# Low_Voltage_Solar_Controller_V1_1.net
KiCad netlist of a schematic drawn in EAGLE
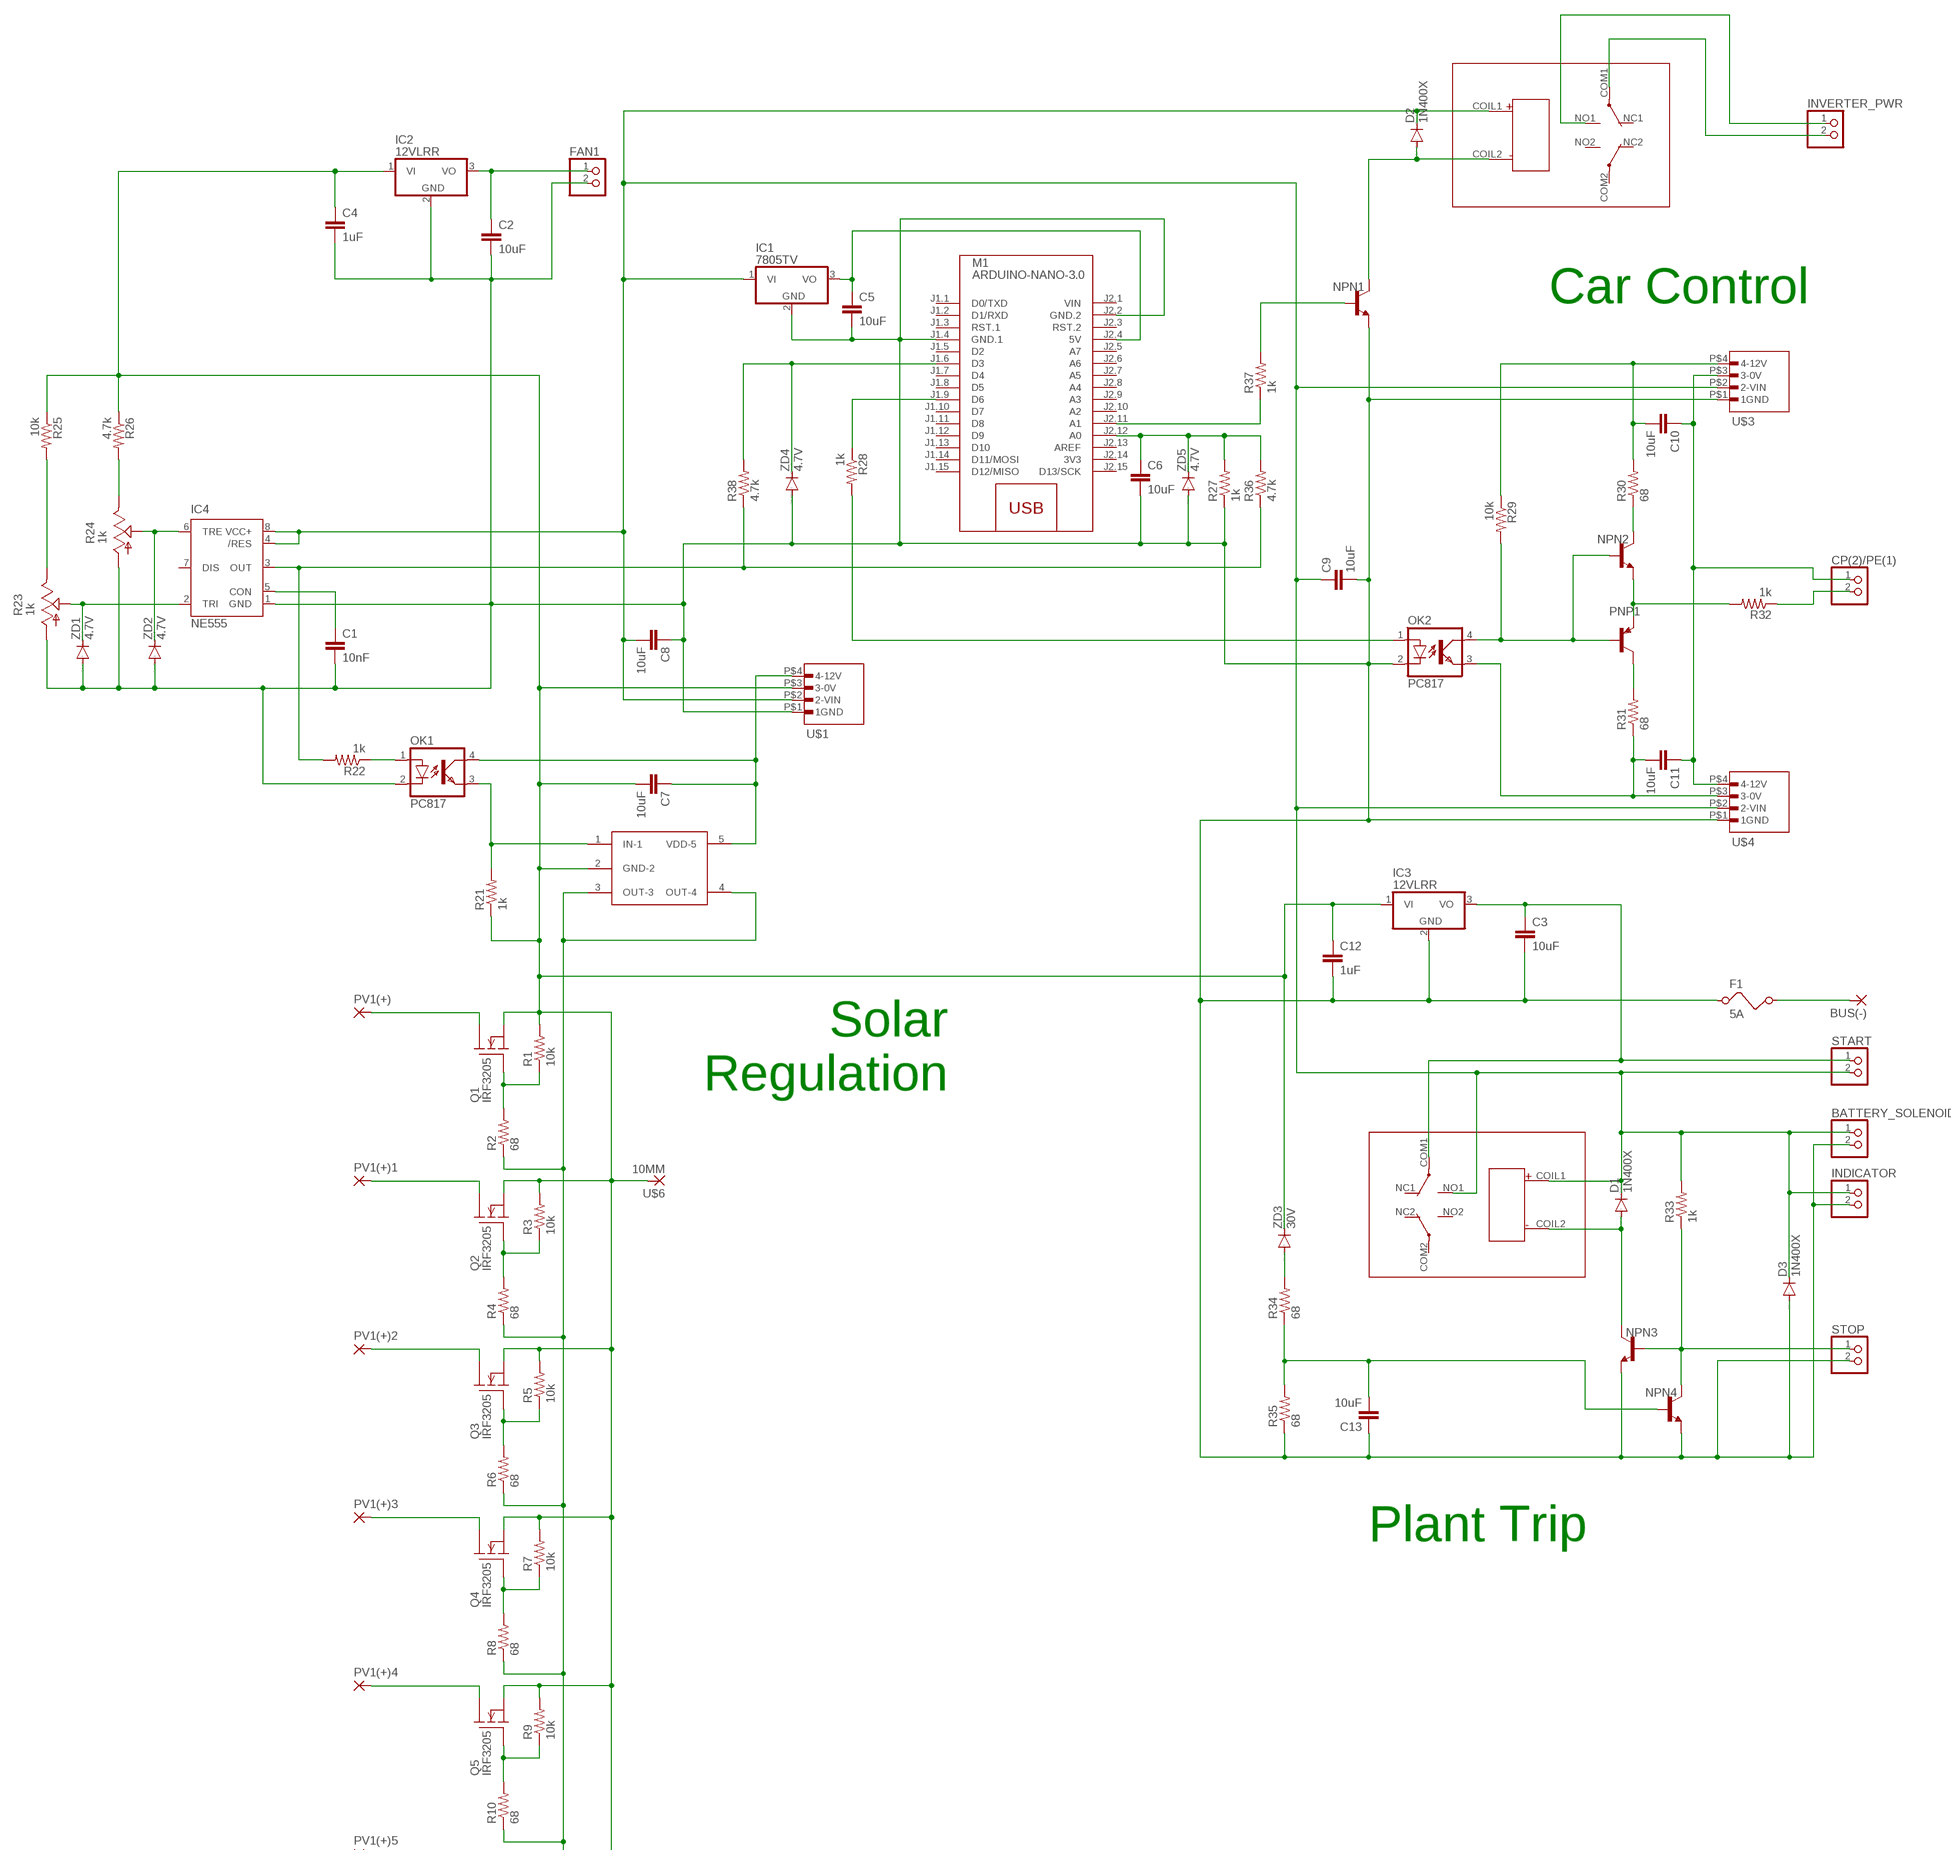
[diagram p0: schematic, sheet 1, part 1 of 2]
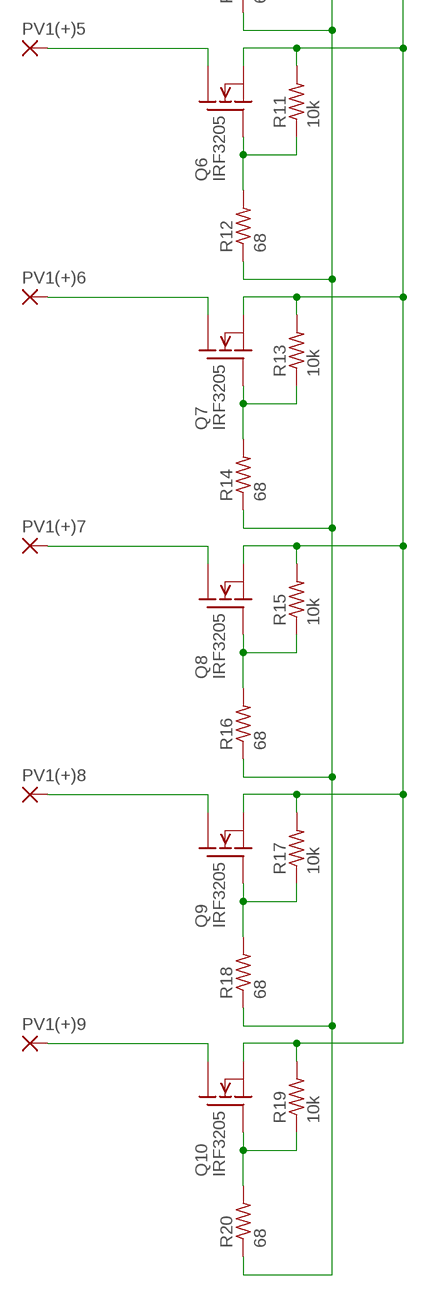
[diagram p1: schematic, sheet 1, part 2 of 2]

(export (version "E")
  (design (tool "Eeschema 10.0.6"))
  (components
    (comp (ref "BATTERY_SOLENOID")
      (value "PINHD-1X2")
      (footprint "eagle-import:1X02")
      (libsource (lib "eagle-import") (part "PINHD-1X2"))
    )
    (comp (ref "BUS(-)")
      (value "5MM_PAD")
      (footprint "eagle-import:5MM")
      (libsource (lib "eagle-import") (part "5MM_PAD"))
    )
    (comp (ref "C1")
      (value "10nF")
      (footprint "eagle-import:C0603")
      (libsource (lib "eagle-import") (part "C-EUC0603"))
    )
    (comp (ref "C2")
      (value "10uF")
      (footprint "eagle-import:C0805")
      (libsource (lib "eagle-import") (part "C-EUC0805"))
    )
    (comp (ref "C3")
      (value "10uF")
      (footprint "eagle-import:C0805")
      (libsource (lib "eagle-import") (part "C-EUC0805"))
    )
    (comp (ref "C4")
      (value "1uF")
      (footprint "eagle-import:C0805")
      (libsource (lib "eagle-import") (part "C-EUC0805"))
    )
    (comp (ref "C5")
      (value "10uF")
      (footprint "eagle-import:C0805")
      (libsource (lib "eagle-import") (part "C-EUC0805"))
    )
    (comp (ref "C6")
      (value "10uF")
      (footprint "eagle-import:C0805")
      (libsource (lib "eagle-import") (part "C-EUC0805"))
    )
    (comp (ref "C7")
      (value "10uF")
      (footprint "eagle-import:C0805")
      (libsource (lib "eagle-import") (part "C-EUC0805"))
    )
    (comp (ref "C8")
      (value "10uF")
      (footprint "eagle-import:C0805")
      (libsource (lib "eagle-import") (part "C-EUC0805"))
    )
    (comp (ref "C9")
      (value "10uF")
      (footprint "eagle-import:C0805")
      (libsource (lib "eagle-import") (part "C-EUC0805"))
    )
    (comp (ref "C10")
      (value "10uF")
      (footprint "eagle-import:C0805")
      (libsource (lib "eagle-import") (part "C-EUC0805"))
    )
    (comp (ref "C11")
      (value "10uF")
      (footprint "eagle-import:C0805")
      (libsource (lib "eagle-import") (part "C-EUC0805"))
    )
    (comp (ref "C12")
      (value "1uF")
      (footprint "eagle-import:C0805")
      (libsource (lib "eagle-import") (part "C-EUC0805"))
    )
    (comp (ref "C13")
      (value "10uF")
      (footprint "eagle-import:C0805")
      (libsource (lib "eagle-import") (part "C-EUC0805"))
    )
    (comp (ref "CP(2)/PE(1)")
      (value "PINHD-1X2")
      (footprint "eagle-import:1X02")
      (libsource (lib "eagle-import") (part "PINHD-1X2"))
    )
    (comp (ref "D1")
      (value "1N400X")
      (footprint "eagle-import:DO41-10")
      (libsource (lib "eagle-import") (part "1N4004"))
    )
    (comp (ref "D2")
      (value "1N400X")
      (footprint "eagle-import:DO41-10")
      (libsource (lib "eagle-import") (part "1N4004"))
    )
    (comp (ref "D3")
      (value "1N400X")
      (footprint "eagle-import:DO41-10")
      (libsource (lib "eagle-import") (part "1N4004"))
    )
    (comp (ref "F1")
      (value "5A")
      (footprint "eagle-import:FUSE_HOLDER")
      (libsource (lib "eagle-import") (part "FUSE_HOLDER"))
    )
    (comp (ref "FAN1")
      (value "PINHD-1X2")
      (footprint "eagle-import:1X02")
      (libsource (lib "eagle-import") (part "PINHD-1X2"))
    )
    (comp (ref "IC1")
      (value "7805TV")
      (footprint "eagle-import:TO220V")
      (libsource (lib "eagle-import") (part "78TV05"))
    )
    (comp (ref "IC2")
      (value "12VLRR")
      (footprint "eagle-import:TO220V")
      (libsource (lib "eagle-import") (part "78TV05"))
    )
    (comp (ref "IC3")
      (value "12VLRR")
      (footprint "eagle-import:TO220V")
      (libsource (lib "eagle-import") (part "78TV05"))
    )
    (comp (ref "IC4")
      (value "NE555")
      (footprint "eagle-import:DIL-08")
      (fields (field (name "MF") "Arrow Electronics") (field (name "MPN") "NE555N"))
      (libsource (lib "eagle-import") (part "NE555"))
    )
    (comp (ref "INDICATOR")
      (value "PINHD-1X2")
      (footprint "eagle-import:1X02")
      (libsource (lib "eagle-import") (part "PINHD-1X2"))
    )
    (comp (ref "INVERTER_PWR")
      (value "PINHD-1X2")
      (footprint "eagle-import:1X02")
      (libsource (lib "eagle-import") (part "PINHD-1X2"))
    )
    (comp (ref "M1")
      (value "ARDUINO-NANO-3.0")
      (footprint "eagle-import:ARDUINO-NANO-3.0")
      (libsource (lib "eagle-import") (part "ARDUINO-NANO-3.0"))
    )
    (comp (ref "NPN1")
      (value "-NPN-TO92-EBC")
      (footprint "eagle-import:TO92-EBC")
      (libsource (lib "eagle-import") (part "-NPN-TO92-EBC"))
    )
    (comp (ref "NPN2")
      (value "-NPN-TO92-EBC")
      (footprint "eagle-import:TO92-EBC")
      (libsource (lib "eagle-import") (part "-NPN-TO92-EBC"))
    )
    (comp (ref "NPN3")
      (value "-NPN-TO92-EBC")
      (footprint "eagle-import:TO92-EBC")
      (libsource (lib "eagle-import") (part "-NPN-TO92-EBC"))
    )
    (comp (ref "NPN4")
      (value "-NPN-TO92-EBC")
      (footprint "eagle-import:TO92-EBC")
      (libsource (lib "eagle-import") (part "-NPN-TO92-EBC"))
    )
    (comp (ref "OK1")
      (value "PC817")
      (footprint "eagle-import:DIL04")
      (fields (field (name "MPN") "PC817X4J000F"))
      (libsource (lib "eagle-import") (part "PC817"))
    )
    (comp (ref "OK2")
      (value "PC817")
      (footprint "eagle-import:DIL04")
      (fields (field (name "MPN") "PC817X4J000F"))
      (libsource (lib "eagle-import") (part "PC817"))
    )
    (comp (ref "PNP1")
      (value "BCX58-PNP-TO92-EBC")
      (footprint "eagle-import:TO92-EBC")
      (libsource (lib "eagle-import") (part "-PNP-TO92-EBCBCX58"))
    )
    (comp (ref "PV1(+)")
      (value "5MM_PAD")
      (footprint "eagle-import:5MM")
      (libsource (lib "eagle-import") (part "5MM_PAD"))
    )
    (comp (ref "PV1(+)1")
      (value "5MM_PAD")
      (footprint "eagle-import:5MM")
      (libsource (lib "eagle-import") (part "5MM_PAD"))
    )
    (comp (ref "PV1(+)2")
      (value "5MM_PAD")
      (footprint "eagle-import:5MM")
      (libsource (lib "eagle-import") (part "5MM_PAD"))
    )
    (comp (ref "PV1(+)3")
      (value "5MM_PAD")
      (footprint "eagle-import:5MM")
      (libsource (lib "eagle-import") (part "5MM_PAD"))
    )
    (comp (ref "PV1(+)4")
      (value "5MM_PAD")
      (footprint "eagle-import:5MM")
      (libsource (lib "eagle-import") (part "5MM_PAD"))
    )
    (comp (ref "PV1(+)5")
      (value "5MM_PAD")
      (footprint "eagle-import:5MM")
      (libsource (lib "eagle-import") (part "5MM_PAD"))
    )
    (comp (ref "PV1(+)6")
      (value "5MM_PAD")
      (footprint "eagle-import:5MM")
      (libsource (lib "eagle-import") (part "5MM_PAD"))
    )
    (comp (ref "PV1(+)7")
      (value "5MM_PAD")
      (footprint "eagle-import:5MM")
      (libsource (lib "eagle-import") (part "5MM_PAD"))
    )
    (comp (ref "PV1(+)8")
      (value "5MM_PAD")
      (footprint "eagle-import:5MM")
      (libsource (lib "eagle-import") (part "5MM_PAD"))
    )
    (comp (ref "PV1(+)9")
      (value "5MM_PAD")
      (footprint "eagle-import:5MM")
      (libsource (lib "eagle-import") (part "5MM_PAD"))
    )
    (comp (ref "Q1")
      (value "IRF3205")
      (footprint "eagle-import:TO220")
      (libsource (lib "eagle-import") (part "BUZ11"))
    )
    (comp (ref "Q2")
      (value "IRF3205")
      (footprint "eagle-import:TO220")
      (libsource (lib "eagle-import") (part "BUZ11"))
    )
    (comp (ref "Q3")
      (value "IRF3205")
      (footprint "eagle-import:TO220")
      (libsource (lib "eagle-import") (part "BUZ11"))
    )
    (comp (ref "Q4")
      (value "IRF3205")
      (footprint "eagle-import:TO220")
      (libsource (lib "eagle-import") (part "BUZ11"))
    )
    (comp (ref "Q5")
      (value "IRF3205")
      (footprint "eagle-import:TO220")
      (libsource (lib "eagle-import") (part "BUZ11"))
    )
    (comp (ref "Q6")
      (value "IRF3205")
      (footprint "eagle-import:TO220")
      (libsource (lib "eagle-import") (part "BUZ11"))
    )
    (comp (ref "Q7")
      (value "IRF3205")
      (footprint "eagle-import:TO220")
      (libsource (lib "eagle-import") (part "BUZ11"))
    )
    (comp (ref "Q8")
      (value "IRF3205")
      (footprint "eagle-import:TO220")
      (libsource (lib "eagle-import") (part "BUZ11"))
    )
    (comp (ref "Q9")
      (value "IRF3205")
      (footprint "eagle-import:TO220")
      (libsource (lib "eagle-import") (part "BUZ11"))
    )
    (comp (ref "Q10")
      (value "IRF3205")
      (footprint "eagle-import:TO220")
      (libsource (lib "eagle-import") (part "BUZ11"))
    )
    (comp (ref "R1")
      (value "10k")
      (footprint "eagle-import:R0805")
      (libsource (lib "eagle-import") (part "R-US_R0805"))
    )
    (comp (ref "R2")
      (value "68")
      (footprint "eagle-import:R0805")
      (libsource (lib "eagle-import") (part "R-US_R0805"))
    )
    (comp (ref "R3")
      (value "10k")
      (footprint "eagle-import:R0805")
      (libsource (lib "eagle-import") (part "R-US_R0805"))
    )
    (comp (ref "R4")
      (value "68")
      (footprint "eagle-import:R0805")
      (libsource (lib "eagle-import") (part "R-US_R0805"))
    )
    (comp (ref "R5")
      (value "10k")
      (footprint "eagle-import:R0805")
      (libsource (lib "eagle-import") (part "R-US_R0805"))
    )
    (comp (ref "R6")
      (value "68")
      (footprint "eagle-import:R0805")
      (libsource (lib "eagle-import") (part "R-US_R0805"))
    )
    (comp (ref "R7")
      (value "10k")
      (footprint "eagle-import:R0805")
      (libsource (lib "eagle-import") (part "R-US_R0805"))
    )
    (comp (ref "R8")
      (value "68")
      (footprint "eagle-import:R0805")
      (libsource (lib "eagle-import") (part "R-US_R0805"))
    )
    (comp (ref "R9")
      (value "10k")
      (footprint "eagle-import:R0805")
      (libsource (lib "eagle-import") (part "R-US_R0805"))
    )
    (comp (ref "R10")
      (value "68")
      (footprint "eagle-import:R0805")
      (libsource (lib "eagle-import") (part "R-US_R0805"))
    )
    (comp (ref "R11")
      (value "10k")
      (footprint "eagle-import:R0805")
      (libsource (lib "eagle-import") (part "R-US_R0805"))
    )
    (comp (ref "R12")
      (value "68")
      (footprint "eagle-import:R0805")
      (libsource (lib "eagle-import") (part "R-US_R0805"))
    )
    (comp (ref "R13")
      (value "10k")
      (footprint "eagle-import:R0805")
      (libsource (lib "eagle-import") (part "R-US_R0805"))
    )
    (comp (ref "R14")
      (value "68")
      (footprint "eagle-import:R0805")
      (libsource (lib "eagle-import") (part "R-US_R0805"))
    )
    (comp (ref "R15")
      (value "10k")
      (footprint "eagle-import:R0805")
      (libsource (lib "eagle-import") (part "R-US_R0805"))
    )
    (comp (ref "R16")
      (value "68")
      (footprint "eagle-import:R0805")
      (libsource (lib "eagle-import") (part "R-US_R0805"))
    )
    (comp (ref "R17")
      (value "10k")
      (footprint "eagle-import:R0805")
      (libsource (lib "eagle-import") (part "R-US_R0805"))
    )
    (comp (ref "R18")
      (value "68")
      (footprint "eagle-import:R0805")
      (libsource (lib "eagle-import") (part "R-US_R0805"))
    )
    (comp (ref "R19")
      (value "10k")
      (footprint "eagle-import:R0805")
      (libsource (lib "eagle-import") (part "R-US_R0805"))
    )
    (comp (ref "R20")
      (value "68")
      (footprint "eagle-import:R0805")
      (libsource (lib "eagle-import") (part "R-US_R0805"))
    )
    (comp (ref "R21")
      (value "1k")
      (footprint "eagle-import:R0805")
      (libsource (lib "eagle-import") (part "R-US_R0805"))
    )
    (comp (ref "R22")
      (value "1k")
      (footprint "eagle-import:R0805")
      (libsource (lib "eagle-import") (part "R-US_R0805"))
    )
    (comp (ref "R23")
      (value "1k")
      (footprint "eagle-import:RJ9W")
      (libsource (lib "eagle-import") (part "TRIM_US-RJ9W"))
    )
    (comp (ref "R24")
      (value "1k")
      (footprint "eagle-import:RJ9W")
      (libsource (lib "eagle-import") (part "TRIM_US-RJ9W"))
    )
    (comp (ref "R25")
      (value "10k")
      (footprint "eagle-import:R0805")
      (libsource (lib "eagle-import") (part "R-US_R0805"))
    )
    (comp (ref "R26")
      (value "4.7k")
      (footprint "eagle-import:R0805")
      (libsource (lib "eagle-import") (part "R-US_R0805"))
    )
    (comp (ref "R27")
      (value "1k")
      (footprint "eagle-import:R0805")
      (libsource (lib "eagle-import") (part "R-US_R0805"))
    )
    (comp (ref "R28")
      (value "1k")
      (footprint "eagle-import:R0805")
      (libsource (lib "eagle-import") (part "R-US_R0805"))
    )
    (comp (ref "R29")
      (value "10k")
      (footprint "eagle-import:R0805")
      (libsource (lib "eagle-import") (part "R-US_R0805"))
    )
    (comp (ref "R30")
      (value "68")
      (footprint "eagle-import:R0805")
      (libsource (lib "eagle-import") (part "R-US_R0805"))
    )
    (comp (ref "R31")
      (value "68")
      (footprint "eagle-import:R0805")
      (libsource (lib "eagle-import") (part "R-US_R0805"))
    )
    (comp (ref "R32")
      (value "1k")
      (footprint "eagle-import:R0805")
      (libsource (lib "eagle-import") (part "R-US_R0805"))
    )
    (comp (ref "R33")
      (value "1k")
      (footprint "eagle-import:R0805")
      (libsource (lib "eagle-import") (part "R-US_R0805"))
    )
    (comp (ref "R34")
      (value "68")
      (footprint "eagle-import:R0805")
      (libsource (lib "eagle-import") (part "R-US_R0805"))
    )
    (comp (ref "R35")
      (value "68")
      (footprint "eagle-import:R0805")
      (libsource (lib "eagle-import") (part "R-US_R0805"))
    )
    (comp (ref "R36")
      (value "4.7k")
      (footprint "eagle-import:R0805")
      (libsource (lib "eagle-import") (part "R-US_R0805"))
    )
    (comp (ref "R37")
      (value "1k")
      (footprint "eagle-import:R0805")
      (libsource (lib "eagle-import") (part "R-US_R0805"))
    )
    (comp (ref "R38")
      (value "4.7k")
      (footprint "eagle-import:R0805")
      (libsource (lib "eagle-import") (part "R-US_R0805"))
    )
    (comp (ref "START")
      (value "PINHD-1X2")
      (footprint "eagle-import:1X02")
      (libsource (lib "eagle-import") (part "PINHD-1X2"))
    )
    (comp (ref "STOP")
      (value "PINHD-1X2")
      (footprint "eagle-import:1X02")
      (libsource (lib "eagle-import") (part "PINHD-1X2"))
    )
    (comp (ref "U$1")
      (value "IB0512S-W75R3")
      (footprint "eagle-import:IB0512S-W75R3")
      (libsource (lib "eagle-import") (part "IB0512S-W75R3"))
    )
    (comp (ref "U$2")
      (value "NCP51100")
      (footprint "eagle-import:SOT23-5")
      (libsource (lib "eagle-import") (part "NCP51100"))
    )
    (comp (ref "U$3")
      (value "IB0512S-W75R3")
      (footprint "eagle-import:IB0512S-W75R3")
      (libsource (lib "eagle-import") (part "IB0512S-W75R3"))
    )
    (comp (ref "U$4")
      (value "IB0512S-W75R3")
      (footprint "eagle-import:IB0512S-W75R3")
      (libsource (lib "eagle-import") (part "IB0512S-W75R3"))
    )
    (comp (ref "U$5")
      (value "J104D2C12VDC.20S")
      (footprint "eagle-import:J104D2C12VDC.20S")
      (libsource (lib "eagle-import") (part "J104D2C12VDC.20S"))
    )
    (comp (ref "U$6")
      (value "10MM")
      (footprint "eagle-import:10MM")
      (libsource (lib "eagle-import") (part "10MM"))
    )
    (comp (ref "U$8")
      (value "J104D2C12VDC.20S")
      (footprint "eagle-import:J104D2C12VDC.20S")
      (libsource (lib "eagle-import") (part "J104D2C12VDC.20S"))
    )
    (comp (ref "ZD1")
      (value "4.7V")
      (footprint "eagle-import:SOD-123_MINI-SMA")
      (libsource (lib "eagle-import") (part "CGRM400-G1"))
    )
    (comp (ref "ZD2")
      (value "4.7V")
      (footprint "eagle-import:SOD-123_MINI-SMA")
      (libsource (lib "eagle-import") (part "CGRM400-G1"))
    )
    (comp (ref "ZD3")
      (value "30V")
      (footprint "eagle-import:DO214AA")
      (libsource (lib "eagle-import") (part "DIODE-DO214AA"))
    )
    (comp (ref "ZD4")
      (value "4.7V")
      (footprint "eagle-import:SOD-123_MINI-SMA")
      (libsource (lib "eagle-import") (part "CGRM400-G1"))
    )
    (comp (ref "ZD5")
      (value "4.7V")
      (footprint "eagle-import:SOD-123_MINI-SMA")
      (libsource (lib "eagle-import") (part "CGRM400-G1"))
    )
  )
  (nets
    (net (code "1") (name "/3V3") (class "Default")
      (node (ref "M1") (pin "J2.14") (pinfunction "3V3_J2.14") (pintype "power_in"))
    )
    (net (code "2") (name "/VIN") (class "Default")
      (node (ref "M1") (pin "J2.1") (pinfunction "VIN_J2.1") (pintype "power_in"))
    )
    (net (code "3") (name "Net-(BUS(-)-P)") (class "Default")
      (node (ref "BUS(-)") (pin "P$1") (pinfunction "P_P$1") (pintype "passive"))
      (node (ref "F1") (pin "P$3") (pinfunction "2_P$3") (pintype "passive"))
      (node (ref "F1") (pin "P$4") (pinfunction "2_P$4") (pintype "passive"))
    )
    (net (code "4") (name "Net-(C13-Pad2)") (class "Default")
      (node (ref "C13") (pin "2") (pinfunction "2_2") (pintype "passive"))
      (node (ref "NPN4") (pin "B") (pinfunction "B_B") (pintype "passive"))
      (node (ref "R34") (pin "1") (pinfunction "1_1") (pintype "passive"))
      (node (ref "R35") (pin "2") (pinfunction "2_2") (pintype "passive"))
    )
    (net (code "5") (name "Net-(CP(2)/PE(1)-Pad2)") (class "Default")
      (node (ref "CP(2)/PE(1)") (pin "2") (pinfunction "2_2") (pintype "passive"))
      (node (ref "R32") (pin "1") (pinfunction "1_1") (pintype "passive"))
    )
    (net (code "6") (name "Net-(D1-PadA)") (class "Default")
      (node (ref "D1") (pin "A") (pinfunction "A_A") (pintype "passive"))
      (node (ref "NPN3") (pin "C") (pinfunction "C_C") (pintype "passive"))
      (node (ref "U$8") (pin "COIL2") (pinfunction "COIL2_COIL2") (pintype "bidirectional"))
    )
    (net (code "7") (name "Net-(D2-PadA)") (class "Default")
      (node (ref "D2") (pin "A") (pinfunction "A_A") (pintype "passive"))
      (node (ref "NPN1") (pin "C") (pinfunction "C_C") (pintype "passive"))
      (node (ref "U$5") (pin "COIL2") (pinfunction "COIL2_COIL2") (pintype "bidirectional"))
    )
    (net (code "8") (name "Net-(IC1-GND)") (class "Default")
      (node (ref "BATTERY_SOLENOID") (pin "2") (pinfunction "2_2") (pintype "passive"))
      (node (ref "C1") (pin "2") (pinfunction "2_2") (pintype "passive"))
      (node (ref "C12") (pin "2") (pinfunction "2_2") (pintype "passive"))
      (node (ref "C13") (pin "1") (pinfunction "1_1") (pintype "passive"))
      (node (ref "C2") (pin "2") (pinfunction "2_2") (pintype "passive"))
      (node (ref "C3") (pin "2") (pinfunction "2_2") (pintype "passive"))
      (node (ref "C4") (pin "2") (pinfunction "2_2") (pintype "passive"))
      (node (ref "C5") (pin "2") (pinfunction "2_2") (pintype "passive"))
      (node (ref "C6") (pin "2") (pinfunction "2_2") (pintype "passive"))
      (node (ref "C8") (pin "1") (pinfunction "1_1") (pintype "passive"))
      (node (ref "C9") (pin "2") (pinfunction "2_2") (pintype "passive"))
      (node (ref "D3") (pin "A") (pinfunction "A_A") (pintype "passive"))
      (node (ref "F1") (pin "P$1") (pinfunction "1_P$1") (pintype "passive"))
      (node (ref "F1") (pin "P$2") (pinfunction "1_P$2") (pintype "passive"))
      (node (ref "FAN1") (pin "2") (pinfunction "2_2") (pintype "passive"))
      (node (ref "IC1") (pin "2") (pinfunction "GND_2") (pintype "passive"))
      (node (ref "IC2") (pin "2") (pinfunction "GND_2") (pintype "passive"))
      (node (ref "IC3") (pin "2") (pinfunction "GND_2") (pintype "passive"))
      (node (ref "IC4") (pin "1") (pinfunction "GND_1") (pintype "power_in"))
      (node (ref "INDICATOR") (pin "2") (pinfunction "2_2") (pintype "passive"))
      (node (ref "M1") (pin "J1.4") (pinfunction "GND.1_J1.4") (pintype "power_in"))
      (node (ref "M1") (pin "J2.2") (pinfunction "GND.2_J2.2") (pintype "power_in"))
      (node (ref "NPN1") (pin "E") (pinfunction "E_E") (pintype "passive"))
      (node (ref "NPN3") (pin "E") (pinfunction "E_E") (pintype "passive"))
      (node (ref "NPN4") (pin "E") (pinfunction "E_E") (pintype "passive"))
      (node (ref "OK1") (pin "2") (pinfunction "C_2") (pintype "passive"))
      (node (ref "OK2") (pin "2") (pinfunction "C_2") (pintype "passive"))
      (node (ref "R23") (pin "A") (pinfunction "A_A") (pintype "passive"))
      (node (ref "R24") (pin "A") (pinfunction "A_A") (pintype "passive"))
      (node (ref "R27") (pin "1") (pinfunction "1_1") (pintype "passive"))
      (node (ref "R35") (pin "1") (pinfunction "1_1") (pintype "passive"))
      (node (ref "STOP") (pin "2") (pinfunction "2_2") (pintype "passive"))
      (node (ref "U$1") (pin "P$1") (pinfunction "1GND_P$1") (pintype "passive"))
      (node (ref "U$3") (pin "P$1") (pinfunction "1GND_P$1") (pintype "passive"))
      (node (ref "U$4") (pin "P$1") (pinfunction "1GND_P$1") (pintype "passive"))
      (node (ref "ZD1") (pin "A") (pinfunction "A_A") (pintype "passive"))
      (node (ref "ZD2") (pin "A") (pinfunction "A_A") (pintype "passive"))
      (node (ref "ZD4") (pin "A") (pinfunction "A_A") (pintype "passive"))
      (node (ref "ZD5") (pin "A") (pinfunction "A_A") (pintype "passive"))
    )
    (net (code "9") (name "Net-(IC1-VI)") (class "Default")
      (node (ref "BATTERY_SOLENOID") (pin "1") (pinfunction "1_1") (pintype "passive"))
      (node (ref "C8") (pin "2") (pinfunction "2_2") (pintype "passive"))
      (node (ref "C9") (pin "1") (pinfunction "1_1") (pintype "passive"))
      (node (ref "D1") (pin "C") (pinfunction "C_C") (pintype "passive"))
      (node (ref "D2") (pin "C") (pinfunction "C_C") (pintype "passive"))
      (node (ref "D3") (pin "C") (pinfunction "C_C") (pintype "passive"))
      (node (ref "IC1") (pin "1") (pinfunction "VI_1") (pintype "input"))
      (node (ref "IC4") (pin "4") (pinfunction "/RES_4") (pintype "input"))
      (node (ref "IC4") (pin "8") (pinfunction "VCC+_8") (pintype "power_in"))
      (node (ref "INDICATOR") (pin "1") (pinfunction "1_1") (pintype "passive"))
      (node (ref "R33") (pin "2") (pinfunction "2_2") (pintype "passive"))
      (node (ref "START") (pin "2") (pinfunction "2_2") (pintype "passive"))
      (node (ref "U$1") (pin "P$2") (pinfunction "2-VIN_P$2") (pintype "passive"))
      (node (ref "U$3") (pin "P$2") (pinfunction "2-VIN_P$2") (pintype "passive"))
      (node (ref "U$4") (pin "P$2") (pinfunction "2-VIN_P$2") (pintype "passive"))
      (node (ref "U$5") (pin "COIL1") (pinfunction "COIL1_COIL1") (pintype "bidirectional"))
      (node (ref "U$8") (pin "COIL1") (pinfunction "COIL1_COIL1") (pintype "bidirectional"))
      (node (ref "U$8") (pin "NO1") (pinfunction "NO1_NO1") (pintype "passive"))
    )
    (net (code "10") (name "Net-(IC1-VO)") (class "Default")
      (node (ref "C5") (pin "1") (pinfunction "1_1") (pintype "passive"))
      (node (ref "IC1") (pin "3") (pinfunction "VO_3") (pintype "passive"))
      (node (ref "M1") (pin "J2.4") (pinfunction "5V_J2.4") (pintype "power_in"))
    )
    (net (code "11") (name "Net-(IC2-VI)") (class "Default")
      (node (ref "C12") (pin "1") (pinfunction "1_1") (pintype "passive"))
      (node (ref "C4") (pin "1") (pinfunction "1_1") (pintype "passive"))
      (node (ref "C7") (pin "2") (pinfunction "2_2") (pintype "passive"))
      (node (ref "IC2") (pin "1") (pinfunction "VI_1") (pintype "input"))
      (node (ref "IC3") (pin "1") (pinfunction "VI_1") (pintype "input"))
      (node (ref "Q1") (pin "3") (pinfunction "S_3") (pintype "passive"))
      (node (ref "Q10") (pin "3") (pinfunction "S_3") (pintype "passive"))
      (node (ref "Q2") (pin "3") (pinfunction "S_3") (pintype "passive"))
      (node (ref "Q3") (pin "3") (pinfunction "S_3") (pintype "passive"))
      (node (ref "Q4") (pin "3") (pinfunction "S_3") (pintype "passive"))
      (node (ref "Q5") (pin "3") (pinfunction "S_3") (pintype "passive"))
      (node (ref "Q6") (pin "3") (pinfunction "S_3") (pintype "passive"))
      (node (ref "Q7") (pin "3") (pinfunction "S_3") (pintype "passive"))
      (node (ref "Q8") (pin "3") (pinfunction "S_3") (pintype "passive"))
      (node (ref "Q9") (pin "3") (pinfunction "S_3") (pintype "passive"))
      (node (ref "R1") (pin "2") (pinfunction "2_2") (pintype "passive"))
      (node (ref "R11") (pin "2") (pinfunction "2_2") (pintype "passive"))
      (node (ref "R13") (pin "2") (pinfunction "2_2") (pintype "passive"))
      (node (ref "R15") (pin "2") (pinfunction "2_2") (pintype "passive"))
      (node (ref "R17") (pin "2") (pinfunction "2_2") (pintype "passive"))
      (node (ref "R19") (pin "2") (pinfunction "2_2") (pintype "passive"))
      (node (ref "R21") (pin "1") (pinfunction "1_1") (pintype "passive"))
      (node (ref "R25") (pin "1") (pinfunction "1_1") (pintype "passive"))
      (node (ref "R26") (pin "1") (pinfunction "1_1") (pintype "passive"))
      (node (ref "R3") (pin "2") (pinfunction "2_2") (pintype "passive"))
      (node (ref "R5") (pin "2") (pinfunction "2_2") (pintype "passive"))
      (node (ref "R7") (pin "2") (pinfunction "2_2") (pintype "passive"))
      (node (ref "R9") (pin "2") (pinfunction "2_2") (pintype "passive"))
      (node (ref "U$1") (pin "P$3") (pinfunction "3-0V_P$3") (pintype "passive"))
      (node (ref "U$2") (pin "2") (pinfunction "GND-2_2") (pintype "bidirectional"))
      (node (ref "U$6") (pin "P$1") (pinfunction "P_P$1") (pintype "passive"))
      (node (ref "ZD3") (pin "C") (pinfunction "C_C") (pintype "passive"))
    )
    (net (code "12") (name "Net-(IC2-VO)") (class "Default")
      (node (ref "C2") (pin "1") (pinfunction "1_1") (pintype "passive"))
      (node (ref "FAN1") (pin "1") (pinfunction "1_1") (pintype "passive"))
      (node (ref "IC2") (pin "3") (pinfunction "VO_3") (pintype "passive"))
    )
    (net (code "13") (name "Net-(IC3-VO)") (class "Default")
      (node (ref "C3") (pin "1") (pinfunction "1_1") (pintype "passive"))
      (node (ref "IC3") (pin "3") (pinfunction "VO_3") (pintype "passive"))
      (node (ref "START") (pin "1") (pinfunction "1_1") (pintype "passive"))
      (node (ref "U$8") (pin "COM1") (pinfunction "COM1_COM1") (pintype "passive"))
    )
    (net (code "14") (name "Net-(IC4-CON)") (class "Default")
      (node (ref "C1") (pin "1") (pinfunction "1_1") (pintype "passive"))
      (node (ref "IC4") (pin "5") (pinfunction "CON_5") (pintype "input"))
    )
    (net (code "15") (name "Net-(IC4-OUT)") (class "Default")
      (node (ref "IC4") (pin "3") (pinfunction "OUT_3") (pintype "output"))
      (node (ref "R22") (pin "2") (pinfunction "2_2") (pintype "passive"))
      (node (ref "R36") (pin "1") (pinfunction "1_1") (pintype "passive"))
      (node (ref "R38") (pin "1") (pinfunction "1_1") (pintype "passive"))
    )
    (net (code "16") (name "Net-(IC4-TRE)") (class "Default")
      (node (ref "IC4") (pin "6") (pinfunction "TRE_6") (pintype "input"))
      (node (ref "R24") (pin "S") (pinfunction "S_S") (pintype "passive"))
      (node (ref "ZD2") (pin "C") (pinfunction "C_C") (pintype "passive"))
    )
    (net (code "17") (name "Net-(IC4-TRI)") (class "Default")
      (node (ref "IC4") (pin "2") (pinfunction "TRI_2") (pintype "input"))
      (node (ref "R23") (pin "S") (pinfunction "S_S") (pintype "passive"))
      (node (ref "ZD1") (pin "C") (pinfunction "C_C") (pintype "passive"))
    )
    (net (code "18") (name "Net-(INVERTER_PWR-Pad1)") (class "Default")
      (node (ref "INVERTER_PWR") (pin "1") (pinfunction "1_1") (pintype "passive"))
      (node (ref "U$5") (pin "NO1") (pinfunction "NO1_NO1") (pintype "passive"))
    )
    (net (code "19") (name "Net-(INVERTER_PWR-Pad2)") (class "Default")
      (node (ref "INVERTER_PWR") (pin "2") (pinfunction "2_2") (pintype "passive"))
      (node (ref "U$5") (pin "COM1") (pinfunction "COM1_COM1") (pintype "passive"))
    )
    (net (code "20") (name "Net-(M1-A0)") (class "Default")
      (node (ref "C6") (pin "1") (pinfunction "1_1") (pintype "passive"))
      (node (ref "M1") (pin "J2.12") (pinfunction "A0_J2.12") (pintype "bidirectional"))
      (node (ref "R27") (pin "2") (pinfunction "2_2") (pintype "passive"))
      (node (ref "R36") (pin "2") (pinfunction "2_2") (pintype "passive"))
      (node (ref "ZD5") (pin "C") (pinfunction "C_C") (pintype "passive"))
    )
    (net (code "21") (name "Net-(M1-A1)") (class "Default")
      (node (ref "M1") (pin "J2.11") (pinfunction "A1_J2.11") (pintype "bidirectional"))
      (node (ref "R37") (pin "1") (pinfunction "1_1") (pintype "passive"))
    )
    (net (code "22") (name "Net-(M1-D3)") (class "Default")
      (node (ref "M1") (pin "J1.6") (pinfunction "D3_J1.6") (pintype "bidirectional"))
      (node (ref "R38") (pin "2") (pinfunction "2_2") (pintype "passive"))
      (node (ref "ZD4") (pin "C") (pinfunction "C_C") (pintype "passive"))
    )
    (net (code "23") (name "Net-(M1-D6)") (class "Default")
      (node (ref "M1") (pin "J1.9") (pinfunction "D6_J1.9") (pintype "bidirectional"))
      (node (ref "R28") (pin "1") (pinfunction "1_1") (pintype "passive"))
    )
    (net (code "24") (name "Net-(NPN1-PadB)") (class "Default")
      (node (ref "NPN1") (pin "B") (pinfunction "B_B") (pintype "passive"))
      (node (ref "R37") (pin "2") (pinfunction "2_2") (pintype "passive"))
    )
    (net (code "25") (name "Net-(NPN2-PadC)") (class "Default")
      (node (ref "NPN2") (pin "C") (pinfunction "C_C") (pintype "passive"))
      (node (ref "R30") (pin "1") (pinfunction "1_1") (pintype "passive"))
    )
    (net (code "26") (name "Net-(NPN2-PadE)") (class "Default")
      (node (ref "NPN2") (pin "E") (pinfunction "E_E") (pintype "passive"))
      (node (ref "PNP1") (pin "E") (pinfunction "E_E") (pintype "passive"))
      (node (ref "R32") (pin "2") (pinfunction "2_2") (pintype "passive"))
    )
    (net (code "27") (name "Net-(NPN3-PadB)") (class "Default")
      (node (ref "NPN3") (pin "B") (pinfunction "B_B") (pintype "passive"))
      (node (ref "NPN4") (pin "C") (pinfunction "C_C") (pintype "passive"))
      (node (ref "R33") (pin "1") (pinfunction "1_1") (pintype "passive"))
      (node (ref "STOP") (pin "1") (pinfunction "1_1") (pintype "passive"))
    )
    (net (code "28") (name "Net-(OK1-A)") (class "Default")
      (node (ref "OK1") (pin "1") (pinfunction "A_1") (pintype "passive"))
      (node (ref "R22") (pin "1") (pinfunction "1_1") (pintype "passive"))
    )
    (net (code "29") (name "Net-(OK1-COL)") (class "Default")
      (node (ref "C7") (pin "1") (pinfunction "1_1") (pintype "passive"))
      (node (ref "OK1") (pin "4") (pinfunction "COL_4") (pintype "passive"))
      (node (ref "U$1") (pin "P$4") (pinfunction "4-12V_P$4") (pintype "passive"))
      (node (ref "U$2") (pin "5") (pinfunction "VDD-5_5") (pintype "bidirectional"))
    )
    (net (code "30") (name "Net-(OK1-EMIT)") (class "Default")
      (node (ref "OK1") (pin "3") (pinfunction "EMIT_3") (pintype "passive"))
      (node (ref "R21") (pin "2") (pinfunction "2_2") (pintype "passive"))
      (node (ref "U$2") (pin "1") (pinfunction "IN-1_1") (pintype "bidirectional"))
    )
    (net (code "31") (name "Net-(OK2-A)") (class "Default")
      (node (ref "OK2") (pin "1") (pinfunction "A_1") (pintype "passive"))
      (node (ref "R28") (pin "2") (pinfunction "2_2") (pintype "passive"))
    )
    (net (code "32") (name "Net-(OK2-COL)") (class "Default")
      (node (ref "NPN2") (pin "B") (pinfunction "B_B") (pintype "passive"))
      (node (ref "OK2") (pin "4") (pinfunction "COL_4") (pintype "passive"))
      (node (ref "PNP1") (pin "B") (pinfunction "B_B") (pintype "passive"))
      (node (ref "R29") (pin "2") (pinfunction "2_2") (pintype "passive"))
    )
    (net (code "33") (name "Net-(OK2-EMIT)") (class "Default")
      (node (ref "C11") (pin "2") (pinfunction "2_2") (pintype "passive"))
      (node (ref "OK2") (pin "3") (pinfunction "EMIT_3") (pintype "passive"))
      (node (ref "R31") (pin "1") (pinfunction "1_1") (pintype "passive"))
      (node (ref "U$4") (pin "P$3") (pinfunction "3-0V_P$3") (pintype "passive"))
    )
    (net (code "34") (name "Net-(PNP1-PadC)") (class "Default")
      (node (ref "PNP1") (pin "C") (pinfunction "C_C") (pintype "passive"))
      (node (ref "R31") (pin "2") (pinfunction "2_2") (pintype "passive"))
    )
    (net (code "35") (name "Net-(PV1(+)-P)") (class "Default")
      (node (ref "PV1(+)") (pin "P$1") (pinfunction "P_P$1") (pintype "passive"))
      (node (ref "Q1") (pin "2") (pinfunction "D_2") (pintype "passive"))
    )
    (net (code "36") (name "Net-(PV1(+)1-P)") (class "Default")
      (node (ref "PV1(+)1") (pin "P$1") (pinfunction "P_P$1") (pintype "passive"))
      (node (ref "Q2") (pin "2") (pinfunction "D_2") (pintype "passive"))
    )
    (net (code "37") (name "Net-(PV1(+)2-P)") (class "Default")
      (node (ref "PV1(+)2") (pin "P$1") (pinfunction "P_P$1") (pintype "passive"))
      (node (ref "Q3") (pin "2") (pinfunction "D_2") (pintype "passive"))
    )
    (net (code "38") (name "Net-(PV1(+)3-P)") (class "Default")
      (node (ref "PV1(+)3") (pin "P$1") (pinfunction "P_P$1") (pintype "passive"))
      (node (ref "Q4") (pin "2") (pinfunction "D_2") (pintype "passive"))
    )
    (net (code "39") (name "Net-(PV1(+)4-P)") (class "Default")
      (node (ref "PV1(+)4") (pin "P$1") (pinfunction "P_P$1") (pintype "passive"))
      (node (ref "Q5") (pin "2") (pinfunction "D_2") (pintype "passive"))
    )
    (net (code "40") (name "Net-(PV1(+)5-P)") (class "Default")
      (node (ref "PV1(+)5") (pin "P$1") (pinfunction "P_P$1") (pintype "passive"))
      (node (ref "Q6") (pin "2") (pinfunction "D_2") (pintype "passive"))
    )
    (net (code "41") (name "Net-(PV1(+)6-P)") (class "Default")
      (node (ref "PV1(+)6") (pin "P$1") (pinfunction "P_P$1") (pintype "passive"))
      (node (ref "Q7") (pin "2") (pinfunction "D_2") (pintype "passive"))
    )
    (net (code "42") (name "Net-(PV1(+)7-P)") (class "Default")
      (node (ref "PV1(+)7") (pin "P$1") (pinfunction "P_P$1") (pintype "passive"))
      (node (ref "Q8") (pin "2") (pinfunction "D_2") (pintype "passive"))
    )
    (net (code "43") (name "Net-(PV1(+)8-P)") (class "Default")
      (node (ref "PV1(+)8") (pin "P$1") (pinfunction "P_P$1") (pintype "passive"))
      (node (ref "Q9") (pin "2") (pinfunction "D_2") (pintype "passive"))
    )
    (net (code "44") (name "Net-(PV1(+)9-P)") (class "Default")
      (node (ref "PV1(+)9") (pin "P$1") (pinfunction "P_P$1") (pintype "passive"))
      (node (ref "Q10") (pin "2") (pinfunction "D_2") (pintype "passive"))
    )
    (net (code "45") (name "Net-(Q1-G)") (class "Default")
      (node (ref "Q1") (pin "1") (pinfunction "G_1") (pintype "passive"))
      (node (ref "R1") (pin "1") (pinfunction "1_1") (pintype "passive"))
      (node (ref "R2") (pin "2") (pinfunction "2_2") (pintype "passive"))
    )
    (net (code "46") (name "Net-(Q2-G)") (class "Default")
      (node (ref "Q2") (pin "1") (pinfunction "G_1") (pintype "passive"))
      (node (ref "R3") (pin "1") (pinfunction "1_1") (pintype "passive"))
      (node (ref "R4") (pin "2") (pinfunction "2_2") (pintype "passive"))
    )
    (net (code "47") (name "Net-(Q3-G)") (class "Default")
      (node (ref "Q3") (pin "1") (pinfunction "G_1") (pintype "passive"))
      (node (ref "R5") (pin "1") (pinfunction "1_1") (pintype "passive"))
      (node (ref "R6") (pin "2") (pinfunction "2_2") (pintype "passive"))
    )
    (net (code "48") (name "Net-(Q4-G)") (class "Default")
      (node (ref "Q4") (pin "1") (pinfunction "G_1") (pintype "passive"))
      (node (ref "R7") (pin "1") (pinfunction "1_1") (pintype "passive"))
      (node (ref "R8") (pin "2") (pinfunction "2_2") (pintype "passive"))
    )
    (net (code "49") (name "Net-(Q5-G)") (class "Default")
      (node (ref "Q5") (pin "1") (pinfunction "G_1") (pintype "passive"))
      (node (ref "R10") (pin "2") (pinfunction "2_2") (pintype "passive"))
      (node (ref "R9") (pin "1") (pinfunction "1_1") (pintype "passive"))
    )
    (net (code "50") (name "Net-(Q6-G)") (class "Default")
      (node (ref "Q6") (pin "1") (pinfunction "G_1") (pintype "passive"))
      (node (ref "R11") (pin "1") (pinfunction "1_1") (pintype "passive"))
      (node (ref "R12") (pin "2") (pinfunction "2_2") (pintype "passive"))
    )
    (net (code "51") (name "Net-(Q7-G)") (class "Default")
      (node (ref "Q7") (pin "1") (pinfunction "G_1") (pintype "passive"))
      (node (ref "R13") (pin "1") (pinfunction "1_1") (pintype "passive"))
      (node (ref "R14") (pin "2") (pinfunction "2_2") (pintype "passive"))
    )
    (net (code "52") (name "Net-(Q8-G)") (class "Default")
      (node (ref "Q8") (pin "1") (pinfunction "G_1") (pintype "passive"))
      (node (ref "R15") (pin "1") (pinfunction "1_1") (pintype "passive"))
      (node (ref "R16") (pin "2") (pinfunction "2_2") (pintype "passive"))
    )
    (net (code "53") (name "Net-(Q9-G)") (class "Default")
      (node (ref "Q9") (pin "1") (pinfunction "G_1") (pintype "passive"))
      (node (ref "R17") (pin "1") (pinfunction "1_1") (pintype "passive"))
      (node (ref "R18") (pin "2") (pinfunction "2_2") (pintype "passive"))
    )
    (net (code "54") (name "Net-(Q10-G)") (class "Default")
      (node (ref "Q10") (pin "1") (pinfunction "G_1") (pintype "passive"))
      (node (ref "R19") (pin "1") (pinfunction "1_1") (pintype "passive"))
      (node (ref "R20") (pin "2") (pinfunction "2_2") (pintype "passive"))
    )
    (net (code "55") (name "Net-(R23-PadE)") (class "Default")
      (node (ref "R23") (pin "E") (pinfunction "E_E") (pintype "passive"))
      (node (ref "R25") (pin "2") (pinfunction "2_2") (pintype "passive"))
    )
    (net (code "56") (name "Net-(R24-PadE)") (class "Default")
      (node (ref "R24") (pin "E") (pinfunction "E_E") (pintype "passive"))
      (node (ref "R26") (pin "2") (pinfunction "2_2") (pintype "passive"))
    )
    (net (code "57") (name "Net-(R34-Pad2)") (class "Default")
      (node (ref "R34") (pin "2") (pinfunction "2_2") (pintype "passive"))
      (node (ref "ZD3") (pin "A") (pinfunction "A_A") (pintype "passive"))
    )
    (net (code "58") (name "Net-(U$2-OUT-3)") (class "Default")
      (node (ref "R10") (pin "1") (pinfunction "1_1") (pintype "passive"))
      (node (ref "R12") (pin "1") (pinfunction "1_1") (pintype "passive"))
      (node (ref "R14") (pin "1") (pinfunction "1_1") (pintype "passive"))
      (node (ref "R16") (pin "1") (pinfunction "1_1") (pintype "passive"))
      (node (ref "R18") (pin "1") (pinfunction "1_1") (pintype "passive"))
      (node (ref "R2") (pin "1") (pinfunction "1_1") (pintype "passive"))
      (node (ref "R20") (pin "1") (pinfunction "1_1") (pintype "passive"))
      (node (ref "R4") (pin "1") (pinfunction "1_1") (pintype "passive"))
      (node (ref "R6") (pin "1") (pinfunction "1_1") (pintype "passive"))
      (node (ref "R8") (pin "1") (pinfunction "1_1") (pintype "passive"))
      (node (ref "U$2") (pin "3") (pinfunction "OUT-3_3") (pintype "bidirectional"))
      (node (ref "U$2") (pin "4") (pinfunction "OUT-4_4") (pintype "bidirectional"))
    )
    (net (code "59") (name "Net-(U$3-3-0V)") (class "Default")
      (node (ref "C10") (pin "1") (pinfunction "1_1") (pintype "passive"))
      (node (ref "C11") (pin "1") (pinfunction "1_1") (pintype "passive"))
      (node (ref "CP(2)/PE(1)") (pin "1") (pinfunction "1_1") (pintype "passive"))
      (node (ref "U$3") (pin "P$3") (pinfunction "3-0V_P$3") (pintype "passive"))
      (node (ref "U$4") (pin "P$4") (pinfunction "4-12V_P$4") (pintype "passive"))
    )
    (net (code "60") (name "Net-(U$3-4-12V)") (class "Default")
      (node (ref "C10") (pin "2") (pinfunction "2_2") (pintype "passive"))
      (node (ref "R29") (pin "1") (pinfunction "1_1") (pintype "passive"))
      (node (ref "R30") (pin "2") (pinfunction "2_2") (pintype "passive"))
      (node (ref "U$3") (pin "P$4") (pinfunction "4-12V_P$4") (pintype "passive"))
    )
    (net (code "61") (name "unconnected-(IC4-DIS-Pad7)") (class "Default")
      (node (ref "IC4") (pin "7") (pinfunction "DIS_7") (pintype "input"))
    )
    (net (code "62") (name "unconnected-(M1-A2-PadJ2.10)") (class "Default")
      (node (ref "M1") (pin "J2.10") (pinfunction "A2_J2.10") (pintype "bidirectional"))
    )
    (net (code "63") (name "unconnected-(M1-A3-PadJ2.9)") (class "Default")
      (node (ref "M1") (pin "J2.9") (pinfunction "A3_J2.9") (pintype "bidirectional"))
    )
    (net (code "64") (name "unconnected-(M1-A4-PadJ2.8)") (class "Default")
      (node (ref "M1") (pin "J2.8") (pinfunction "A4_J2.8") (pintype "bidirectional"))
    )
    (net (code "65") (name "unconnected-(M1-A5-PadJ2.7)") (class "Default")
      (node (ref "M1") (pin "J2.7") (pinfunction "A5_J2.7") (pintype "bidirectional"))
    )
    (net (code "66") (name "unconnected-(M1-A6-PadJ2.6)") (class "Default")
      (node (ref "M1") (pin "J2.6") (pinfunction "A6_J2.6") (pintype "bidirectional"))
    )
    (net (code "67") (name "unconnected-(M1-A7-PadJ2.5)") (class "Default")
      (node (ref "M1") (pin "J2.5") (pinfunction "A7_J2.5") (pintype "bidirectional"))
    )
    (net (code "68") (name "unconnected-(M1-AREF-PadJ2.13)") (class "Default")
      (node (ref "M1") (pin "J2.13") (pinfunction "AREF_J2.13") (pintype "bidirectional"))
    )
    (net (code "69") (name "unconnected-(M1-D0{slash}TXD-PadJ1.1)") (class "Default")
      (node (ref "M1") (pin "J1.1") (pinfunction "D0/TXD_J1.1") (pintype "bidirectional"))
    )
    (net (code "70") (name "unconnected-(M1-D1{slash}RXD-PadJ1.2)") (class "Default")
      (node (ref "M1") (pin "J1.2") (pinfunction "D1/RXD_J1.2") (pintype "bidirectional"))
    )
    (net (code "71") (name "unconnected-(M1-D2-PadJ1.5)") (class "Default")
      (node (ref "M1") (pin "J1.5") (pinfunction "D2_J1.5") (pintype "bidirectional"))
    )
    (net (code "72") (name "unconnected-(M1-D4-PadJ1.7)") (class "Default")
      (node (ref "M1") (pin "J1.7") (pinfunction "D4_J1.7") (pintype "bidirectional"))
    )
    (net (code "73") (name "unconnected-(M1-D5-PadJ1.8)") (class "Default")
      (node (ref "M1") (pin "J1.8") (pinfunction "D5_J1.8") (pintype "bidirectional"))
    )
    (net (code "74") (name "unconnected-(M1-D7-PadJ1.10)") (class "Default")
      (node (ref "M1") (pin "J1.10") (pinfunction "D7_J1.10") (pintype "bidirectional"))
    )
    (net (code "75") (name "unconnected-(M1-D8-PadJ1.11)") (class "Default")
      (node (ref "M1") (pin "J1.11") (pinfunction "D8_J1.11") (pintype "bidirectional"))
    )
    (net (code "76") (name "unconnected-(M1-D9-PadJ1.12)") (class "Default")
      (node (ref "M1") (pin "J1.12") (pinfunction "D9_J1.12") (pintype "bidirectional"))
    )
    (net (code "77") (name "unconnected-(M1-D10-PadJ1.13)") (class "Default")
      (node (ref "M1") (pin "J1.13") (pinfunction "D10_J1.13") (pintype "bidirectional"))
    )
    (net (code "78") (name "unconnected-(M1-D11{slash}MOSI-PadJ1.14)") (class "Default")
      (node (ref "M1") (pin "J1.14") (pinfunction "D11/MOSI_J1.14") (pintype "bidirectional"))
    )
    (net (code "79") (name "unconnected-(M1-D12{slash}MISO-PadJ1.15)") (class "Default")
      (node (ref "M1") (pin "J1.15") (pinfunction "D12/MISO_J1.15") (pintype "bidirectional"))
    )
    (net (code "80") (name "unconnected-(M1-D13{slash}SCK-PadJ2.15)") (class "Default")
      (node (ref "M1") (pin "J2.15") (pinfunction "D13/SCK_J2.15") (pintype "bidirectional"))
    )
    (net (code "81") (name "unconnected-(M1-RST.1-PadJ1.3)") (class "Default")
      (node (ref "M1") (pin "J1.3") (pinfunction "RST.1_J1.3") (pintype "bidirectional"))
    )
    (net (code "82") (name "unconnected-(M1-RST.2-PadJ2.3)") (class "Default")
      (node (ref "M1") (pin "J2.3") (pinfunction "RST.2_J2.3") (pintype "bidirectional"))
    )
    (net (code "83") (name "unconnected-(U$5-PadCOM2)") (class "Default")
      (node (ref "U$5") (pin "COM2") (pinfunction "COM2_COM2") (pintype "passive"))
    )
    (net (code "84") (name "unconnected-(U$5-PadNC1)") (class "Default")
      (node (ref "U$5") (pin "NC1") (pinfunction "NC1_NC1") (pintype "passive"))
    )
    (net (code "85") (name "unconnected-(U$5-PadNC2)") (class "Default")
      (node (ref "U$5") (pin "NC2") (pinfunction "NC2_NC2") (pintype "passive"))
    )
    (net (code "86") (name "unconnected-(U$5-PadNO2)") (class "Default")
      (node (ref "U$5") (pin "NO2") (pinfunction "NO2_NO2") (pintype "passive"))
    )
    (net (code "87") (name "unconnected-(U$8-PadCOM2)") (class "Default")
      (node (ref "U$8") (pin "COM2") (pinfunction "COM2_COM2") (pintype "passive"))
    )
    (net (code "88") (name "unconnected-(U$8-PadNC1)") (class "Default")
      (node (ref "U$8") (pin "NC1") (pinfunction "NC1_NC1") (pintype "passive"))
    )
    (net (code "89") (name "unconnected-(U$8-PadNC2)") (class "Default")
      (node (ref "U$8") (pin "NC2") (pinfunction "NC2_NC2") (pintype "passive"))
    )
    (net (code "90") (name "unconnected-(U$8-PadNO2)") (class "Default")
      (node (ref "U$8") (pin "NO2") (pinfunction "NO2_NO2") (pintype "passive"))
    )
  )
)
